# Non-Isolated_Gate_Driver_and_Supply.net
KiCad netlist of a schematic drawn in Altium Designer
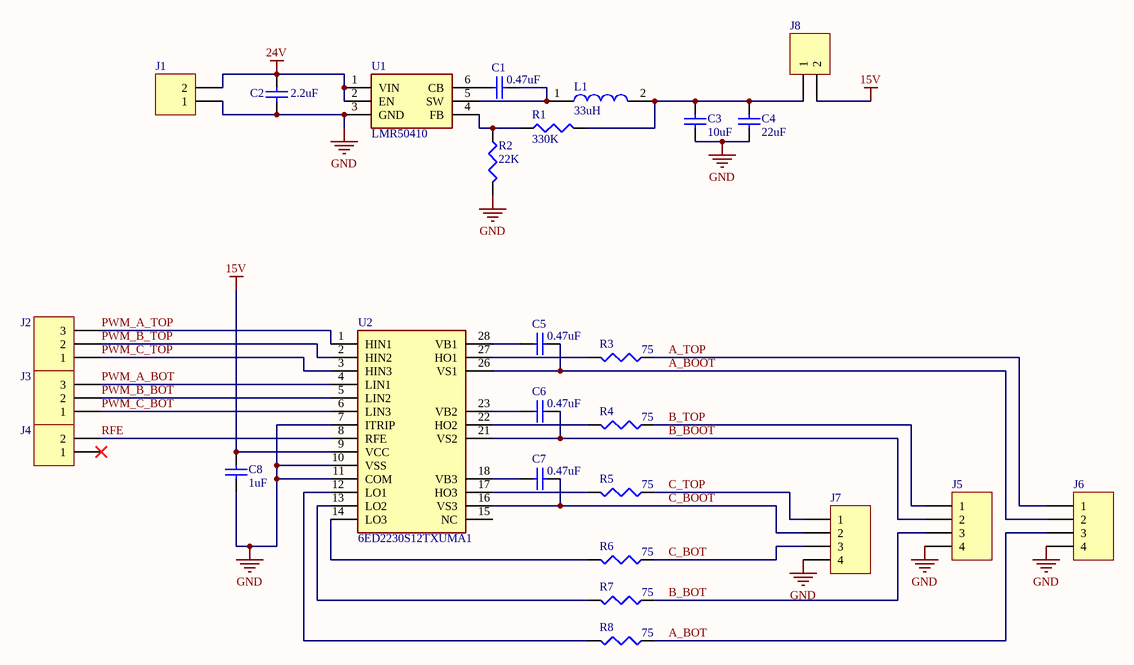
[diagram p0: Non-Isolated Gate Driver and Supply.SchDoc]

(export (version "E")
  (design (tool "Eeschema 10.0.6"))
  (components
    (comp (ref "C1")
      (value "0.47uF")
      (footprint "C0805")
      (description "Capacitor")
      (fields (field (name "Comment") "Cap") (field (name "PUBLISHER") "Altium Limited"))
      (libsource (lib "Miscellaneous Devices") (part "Cap"))
    )
    (comp (ref "C2")
      (value "2.2uF")
      (footprint "C0805")
      (description "Capacitor")
      (fields (field (name "Comment") "Cap") (field (name "PUBLISHER") "Altium Limited"))
      (libsource (lib "Miscellaneous Devices") (part "Cap"))
    )
    (comp (ref "C3")
      (value "10uF")
      (footprint "C0805")
      (description "Capacitor")
      (fields (field (name "Comment") "Cap") (field (name "PUBLISHER") "Altium Limited"))
      (libsource (lib "Miscellaneous Devices") (part "Cap"))
    )
    (comp (ref "C4")
      (value "22uF")
      (footprint "C0805")
      (description "Capacitor")
      (fields (field (name "Comment") "Cap") (field (name "PUBLISHER") "Altium Limited"))
      (libsource (lib "Miscellaneous Devices") (part "Cap"))
    )
    (comp (ref "C5")
      (value "0.47uF")
      (footprint "C1206")
      (description "Capacitor")
      (fields (field (name "Comment") "Cap") (field (name "PUBLISHER") "Altium Limited"))
      (libsource (lib "Miscellaneous Devices") (part "Cap"))
    )
    (comp (ref "C6")
      (value "0.47uF")
      (footprint "C1206")
      (description "Capacitor")
      (fields (field (name "Comment") "Cap") (field (name "PUBLISHER") "Altium Limited"))
      (libsource (lib "Miscellaneous Devices") (part "Cap"))
    )
    (comp (ref "C7")
      (value "0.47uF")
      (footprint "C1206")
      (description "Capacitor")
      (fields (field (name "Comment") "Cap") (field (name "PUBLISHER") "Altium Limited"))
      (libsource (lib "Miscellaneous Devices") (part "Cap"))
    )
    (comp (ref "C8")
      (value "1uF")
      (footprint "C0805")
      (description "Capacitor")
      (fields (field (name "Comment") "Cap") (field (name "PUBLISHER") "Altium Limited"))
      (libsource (lib "Miscellaneous Devices") (part "Cap"))
    )
    (comp (ref "J1")
      (value "Header 2")
      (footprint "HDR1X2")
      (description "Header, 2-Pin")
      (fields (field (name "PUBLISHER") "Altium Limited"))
      (libsource (lib "Miscellaneous Connectors") (part "Header 2"))
    )
    (comp (ref "J2")
      (value "Header 3")
      (footprint "HDR1X3")
      (description "Header, 3-Pin")
      (fields (field (name "PUBLISHER") "Altium Limited"))
      (libsource (lib "Miscellaneous Connectors") (part "Header 3"))
    )
    (comp (ref "J3")
      (value "Header 3")
      (footprint "HDR1X3")
      (description "Header, 3-Pin")
      (fields (field (name "PUBLISHER") "Altium Limited"))
      (libsource (lib "Miscellaneous Connectors") (part "Header 3"))
    )
    (comp (ref "J4")
      (value "Header 2")
      (footprint "HDR1X2")
      (description "Header, 2-Pin")
      (fields (field (name "PUBLISHER") "Altium Limited"))
      (libsource (lib "Miscellaneous Connectors") (part "Header 2"))
    )
    (comp (ref "J5")
      (value "Header 4")
      (footprint "HDR1X4")
      (description "Header, 4-Pin")
      (fields (field (name "PUBLISHER") "Altium Limited"))
      (libsource (lib "Miscellaneous Connectors") (part "Header 4"))
    )
    (comp (ref "J6")
      (value "Header 4")
      (footprint "HDR1X4")
      (description "Header, 4-Pin")
      (fields (field (name "PUBLISHER") "Altium Limited"))
      (libsource (lib "Miscellaneous Connectors") (part "Header 4"))
    )
    (comp (ref "J7")
      (value "Header 4")
      (footprint "HDR1X4")
      (description "Header, 4-Pin")
      (fields (field (name "PUBLISHER") "Altium Limited"))
      (libsource (lib "Miscellaneous Connectors") (part "Header 4"))
    )
    (comp (ref "J8")
      (value "Header 2")
      (footprint "HDR1X2")
      (description "Header, 2-Pin")
      (fields (field (name "PUBLISHER") "Altium Limited"))
      (libsource (lib "") (part "Header 2_1"))
    )
    (comp (ref "L1")
      (value "33uH")
      (footprint "Motor Controller:PM4340682NLT")
      (description "Inductor")
      (fields (field (name "MANUFACTURER_PART_NUMBER") "PM4340.333NLT"))
      (libsource (lib "Motor Controller") (part "PM4340.333NLT"))
    )
    (comp (ref "R1")
      (value "330K")
      (footprint "J1-0603")
      (description "Resistor")
      (fields (field (name "Comment") "Res3") (field (name "PUBLISHER") "Altium Limited"))
      (libsource (lib "Miscellaneous Devices") (part "Res3"))
    )
    (comp (ref "R2")
      (value "22K")
      (footprint "J1-0603")
      (description "Resistor")
      (fields (field (name "Comment") "Res3") (field (name "PUBLISHER") "Altium Limited"))
      (libsource (lib "Miscellaneous Devices") (part "Res3"))
    )
    (comp (ref "R3")
      (value "75")
      (footprint "C1206")
      (description "Resistor")
      (fields (field (name "Comment") "Res3") (field (name "PUBLISHER") "Altium Limited"))
      (libsource (lib "Miscellaneous Devices") (part "Res3"))
    )
    (comp (ref "R4")
      (value "75")
      (footprint "C1206")
      (description "Resistor")
      (fields (field (name "Comment") "Res3") (field (name "PUBLISHER") "Altium Limited"))
      (libsource (lib "Miscellaneous Devices") (part "Res3"))
    )
    (comp (ref "R5")
      (value "75")
      (footprint "C1206")
      (description "Resistor")
      (fields (field (name "Comment") "Res3") (field (name "PUBLISHER") "Altium Limited"))
      (libsource (lib "Miscellaneous Devices") (part "Res3"))
    )
    (comp (ref "R6")
      (value "75")
      (footprint "C1206")
      (description "Resistor")
      (fields (field (name "Comment") "Res3") (field (name "PUBLISHER") "Altium Limited"))
      (libsource (lib "Miscellaneous Devices") (part "Res3"))
    )
    (comp (ref "R7")
      (value "75")
      (footprint "C1206")
      (description "Resistor")
      (fields (field (name "Comment") "Res3") (field (name "PUBLISHER") "Altium Limited"))
      (libsource (lib "Miscellaneous Devices") (part "Res3"))
    )
    (comp (ref "R8")
      (value "75")
      (footprint "C1206")
      (description "Resistor")
      (fields (field (name "Comment") "Res3") (field (name "PUBLISHER") "Altium Limited"))
      (libsource (lib "Miscellaneous Devices") (part "Res3"))
    )
    (comp (ref "U1")
      (value "LMR50410")
      (footprint "Motor Controller:SOT95P280X145-6N")
      (description "Integrated Circuit")
      (libsource (lib "Motor Controller") (part "LMR50410"))
    )
    (comp (ref "U2")
      (value "6ED2230S12TXUMA1")
      (footprint "Motor Controller:SOIC127P1030X265-28N")
      (description "Integrated Circuit")
      (fields (field (name "MOUSER PART NUMBER") "726-6ED2230S12TXUMA1"))
      (libsource (lib "Motor Controller") (part "6ED2230S12TXUMA1"))
    )
  )
  (nets
    (net (code "1") (name "/A_BOOT") (class "Default")
      (node (ref "C5") (pin "1") (pinfunction "1_1") (pintype "passive"))
      (node (ref "J6") (pin "2") (pinfunction "2_2") (pintype "passive"))
      (node (ref "U2") (pin "26") (pinfunction "VS1_26") (pintype "passive"))
    )
    (net (code "2") (name "/A_BOT") (class "Default")
      (node (ref "J6") (pin "3") (pinfunction "3_3") (pintype "passive"))
      (node (ref "R8") (pin "1") (pinfunction "1_1") (pintype "passive"))
    )
    (net (code "3") (name "/A_TOP") (class "Default")
      (node (ref "J6") (pin "1") (pinfunction "1_1") (pintype "passive"))
      (node (ref "R3") (pin "1") (pinfunction "1_1") (pintype "passive"))
    )
    (net (code "4") (name "/B_BOOT") (class "Default")
      (node (ref "C6") (pin "1") (pinfunction "1_1") (pintype "passive"))
      (node (ref "J5") (pin "2") (pinfunction "2_2") (pintype "passive"))
      (node (ref "U2") (pin "21") (pinfunction "VS2_21") (pintype "passive"))
    )
    (net (code "5") (name "/B_BOT") (class "Default")
      (node (ref "J5") (pin "3") (pinfunction "3_3") (pintype "passive"))
      (node (ref "R7") (pin "1") (pinfunction "1_1") (pintype "passive"))
    )
    (net (code "6") (name "/B_TOP") (class "Default")
      (node (ref "J5") (pin "1") (pinfunction "1_1") (pintype "passive"))
      (node (ref "R4") (pin "1") (pinfunction "1_1") (pintype "passive"))
    )
    (net (code "7") (name "/C_BOOT") (class "Default")
      (node (ref "C7") (pin "1") (pinfunction "1_1") (pintype "passive"))
      (node (ref "J7") (pin "2") (pinfunction "2_2") (pintype "passive"))
      (node (ref "U2") (pin "16") (pinfunction "VS3_16") (pintype "passive"))
    )
    (net (code "8") (name "/C_BOT") (class "Default")
      (node (ref "J7") (pin "3") (pinfunction "3_3") (pintype "passive"))
      (node (ref "R6") (pin "1") (pinfunction "1_1") (pintype "passive"))
    )
    (net (code "9") (name "/C_TOP") (class "Default")
      (node (ref "J7") (pin "1") (pinfunction "1_1") (pintype "passive"))
      (node (ref "R5") (pin "1") (pinfunction "1_1") (pintype "passive"))
    )
    (net (code "10") (name "/PWM_A_BOT") (class "Default")
      (node (ref "J3") (pin "3") (pinfunction "3_3") (pintype "passive"))
      (node (ref "U2") (pin "4") (pinfunction "LIN1_4") (pintype "passive"))
    )
    (net (code "11") (name "/PWM_A_TOP") (class "Default")
      (node (ref "J2") (pin "3") (pinfunction "3_3") (pintype "passive"))
      (node (ref "U2") (pin "1") (pinfunction "HIN1_1") (pintype "passive"))
    )
    (net (code "12") (name "/PWM_B_BOT") (class "Default")
      (node (ref "J3") (pin "2") (pinfunction "2_2") (pintype "passive"))
      (node (ref "U2") (pin "5") (pinfunction "LIN2_5") (pintype "passive"))
    )
    (net (code "13") (name "/PWM_B_TOP") (class "Default")
      (node (ref "J2") (pin "2") (pinfunction "2_2") (pintype "passive"))
      (node (ref "U2") (pin "2") (pinfunction "HIN2_2") (pintype "passive"))
    )
    (net (code "14") (name "/PWM_C_BOT") (class "Default")
      (node (ref "J3") (pin "1") (pinfunction "1_1") (pintype "passive"))
      (node (ref "U2") (pin "6") (pinfunction "LIN3_6") (pintype "passive"))
    )
    (net (code "15") (name "/PWM_C_TOP") (class "Default")
      (node (ref "J2") (pin "1") (pinfunction "1_1") (pintype "passive"))
      (node (ref "U2") (pin "3") (pinfunction "HIN3_3") (pintype "passive"))
    )
    (net (code "16") (name "/RFE") (class "Default")
      (node (ref "J4") (pin "2") (pinfunction "2_2") (pintype "passive"))
      (node (ref "U2") (pin "8") (pinfunction "RFE_8") (pintype "passive"))
    )
    (net (code "17") (name "15V") (class "Default")
      (node (ref "C8") (pin "1") (pinfunction "1_1") (pintype "passive"))
      (node (ref "J8") (pin "2") (pinfunction "2_2") (pintype "passive"))
      (node (ref "U2") (pin "9") (pinfunction "VCC_9") (pintype "passive"))
    )
    (net (code "18") (name "24V") (class "Default")
      (node (ref "C2") (pin "1") (pinfunction "1_1") (pintype "passive"))
      (node (ref "J1") (pin "2") (pinfunction "2_2") (pintype "passive"))
      (node (ref "U1") (pin "1") (pinfunction "VIN_1") (pintype "passive"))
      (node (ref "U1") (pin "2") (pinfunction "EN_2") (pintype "passive"))
    )
    (net (code "19") (name "GND") (class "Default")
      (node (ref "C2") (pin "2") (pinfunction "2_2") (pintype "passive"))
      (node (ref "C3") (pin "2") (pinfunction "2_2") (pintype "passive"))
      (node (ref "C4") (pin "2") (pinfunction "2_2") (pintype "passive"))
      (node (ref "C8") (pin "2") (pinfunction "2_2") (pintype "passive"))
      (node (ref "J1") (pin "1") (pinfunction "1_1") (pintype "passive"))
      (node (ref "J5") (pin "4") (pinfunction "4_4") (pintype "passive"))
      (node (ref "J6") (pin "4") (pinfunction "4_4") (pintype "passive"))
      (node (ref "J7") (pin "4") (pinfunction "4_4") (pintype "passive"))
      (node (ref "R2") (pin "2") (pinfunction "2_2") (pintype "passive"))
      (node (ref "U1") (pin "3") (pinfunction "GND_3") (pintype "passive"))
      (node (ref "U2") (pin "10") (pinfunction "VSS_10") (pintype "passive"))
      (node (ref "U2") (pin "11") (pinfunction "COM_11") (pintype "passive"))
      (node (ref "U2") (pin "7") (pinfunction "ITRIP_7") (pintype "passive"))
    )
    (net (code "20") (name "Net-(C3-Pad1)") (class "Default")
      (node (ref "C3") (pin "1") (pinfunction "1_1") (pintype "passive"))
      (node (ref "C4") (pin "1") (pinfunction "1_1") (pintype "passive"))
      (node (ref "J8") (pin "1") (pinfunction "1_1") (pintype "passive"))
      (node (ref "L1") (pin "2") (pinfunction "2_2") (pintype "passive"))
      (node (ref "R1") (pin "2") (pinfunction "2_2") (pintype "passive"))
    )
    (net (code "21") (name "Net-(U1-CB)") (class "Default")
      (node (ref "C1") (pin "1") (pinfunction "1_1") (pintype "passive"))
      (node (ref "U1") (pin "6") (pinfunction "CB_6") (pintype "passive"))
    )
    (net (code "22") (name "Net-(U1-FB)") (class "Default")
      (node (ref "R1") (pin "1") (pinfunction "1_1") (pintype "passive"))
      (node (ref "R2") (pin "1") (pinfunction "1_1") (pintype "passive"))
      (node (ref "U1") (pin "4") (pinfunction "FB_4") (pintype "passive"))
    )
    (net (code "23") (name "Net-(U1-SW)") (class "Default")
      (node (ref "C1") (pin "2") (pinfunction "2_2") (pintype "passive"))
      (node (ref "L1") (pin "1") (pinfunction "1_1") (pintype "passive"))
      (node (ref "U1") (pin "5") (pinfunction "SW_5") (pintype "passive"))
    )
    (net (code "24") (name "Net-(U2-HO1)") (class "Default")
      (node (ref "R3") (pin "2") (pinfunction "2_2") (pintype "passive"))
      (node (ref "U2") (pin "27") (pinfunction "HO1_27") (pintype "passive"))
    )
    (net (code "25") (name "Net-(U2-HO2)") (class "Default")
      (node (ref "R4") (pin "2") (pinfunction "2_2") (pintype "passive"))
      (node (ref "U2") (pin "22") (pinfunction "HO2_22") (pintype "passive"))
    )
    (net (code "26") (name "Net-(U2-HO3)") (class "Default")
      (node (ref "R5") (pin "2") (pinfunction "2_2") (pintype "passive"))
      (node (ref "U2") (pin "17") (pinfunction "HO3_17") (pintype "passive"))
    )
    (net (code "27") (name "Net-(U2-LO1)") (class "Default")
      (node (ref "R8") (pin "2") (pinfunction "2_2") (pintype "passive"))
      (node (ref "U2") (pin "12") (pinfunction "LO1_12") (pintype "passive"))
    )
    (net (code "28") (name "Net-(U2-LO2)") (class "Default")
      (node (ref "R7") (pin "2") (pinfunction "2_2") (pintype "passive"))
      (node (ref "U2") (pin "13") (pinfunction "LO2_13") (pintype "passive"))
    )
    (net (code "29") (name "Net-(U2-LO3)") (class "Default")
      (node (ref "R6") (pin "2") (pinfunction "2_2") (pintype "passive"))
      (node (ref "U2") (pin "14") (pinfunction "LO3_14") (pintype "passive"))
    )
    (net (code "30") (name "Net-(U2-VB1)") (class "Default")
      (node (ref "C5") (pin "2") (pinfunction "2_2") (pintype "passive"))
      (node (ref "U2") (pin "28") (pinfunction "VB1_28") (pintype "passive"))
    )
    (net (code "31") (name "Net-(U2-VB2)") (class "Default")
      (node (ref "C6") (pin "2") (pinfunction "2_2") (pintype "passive"))
      (node (ref "U2") (pin "23") (pinfunction "VB2_23") (pintype "passive"))
    )
    (net (code "32") (name "Net-(U2-VB3)") (class "Default")
      (node (ref "C7") (pin "2") (pinfunction "2_2") (pintype "passive"))
      (node (ref "U2") (pin "18") (pinfunction "VB3_18") (pintype "passive"))
    )
    (net (code "33") (name "unconnected-(J4-Pad1)") (class "Default")
      (node (ref "J4") (pin "1") (pinfunction "1_1") (pintype "passive+no_connect"))
    )
    (net (code "34") (name "unconnected-(U2-NC-Pad15)") (class "Default")
      (node (ref "U2") (pin "15") (pinfunction "NC_15") (pintype "passive"))
    )
  )
)
